# holiday_tree_schematic.net
KiCad netlist of a schematic drawn in Altium Designer
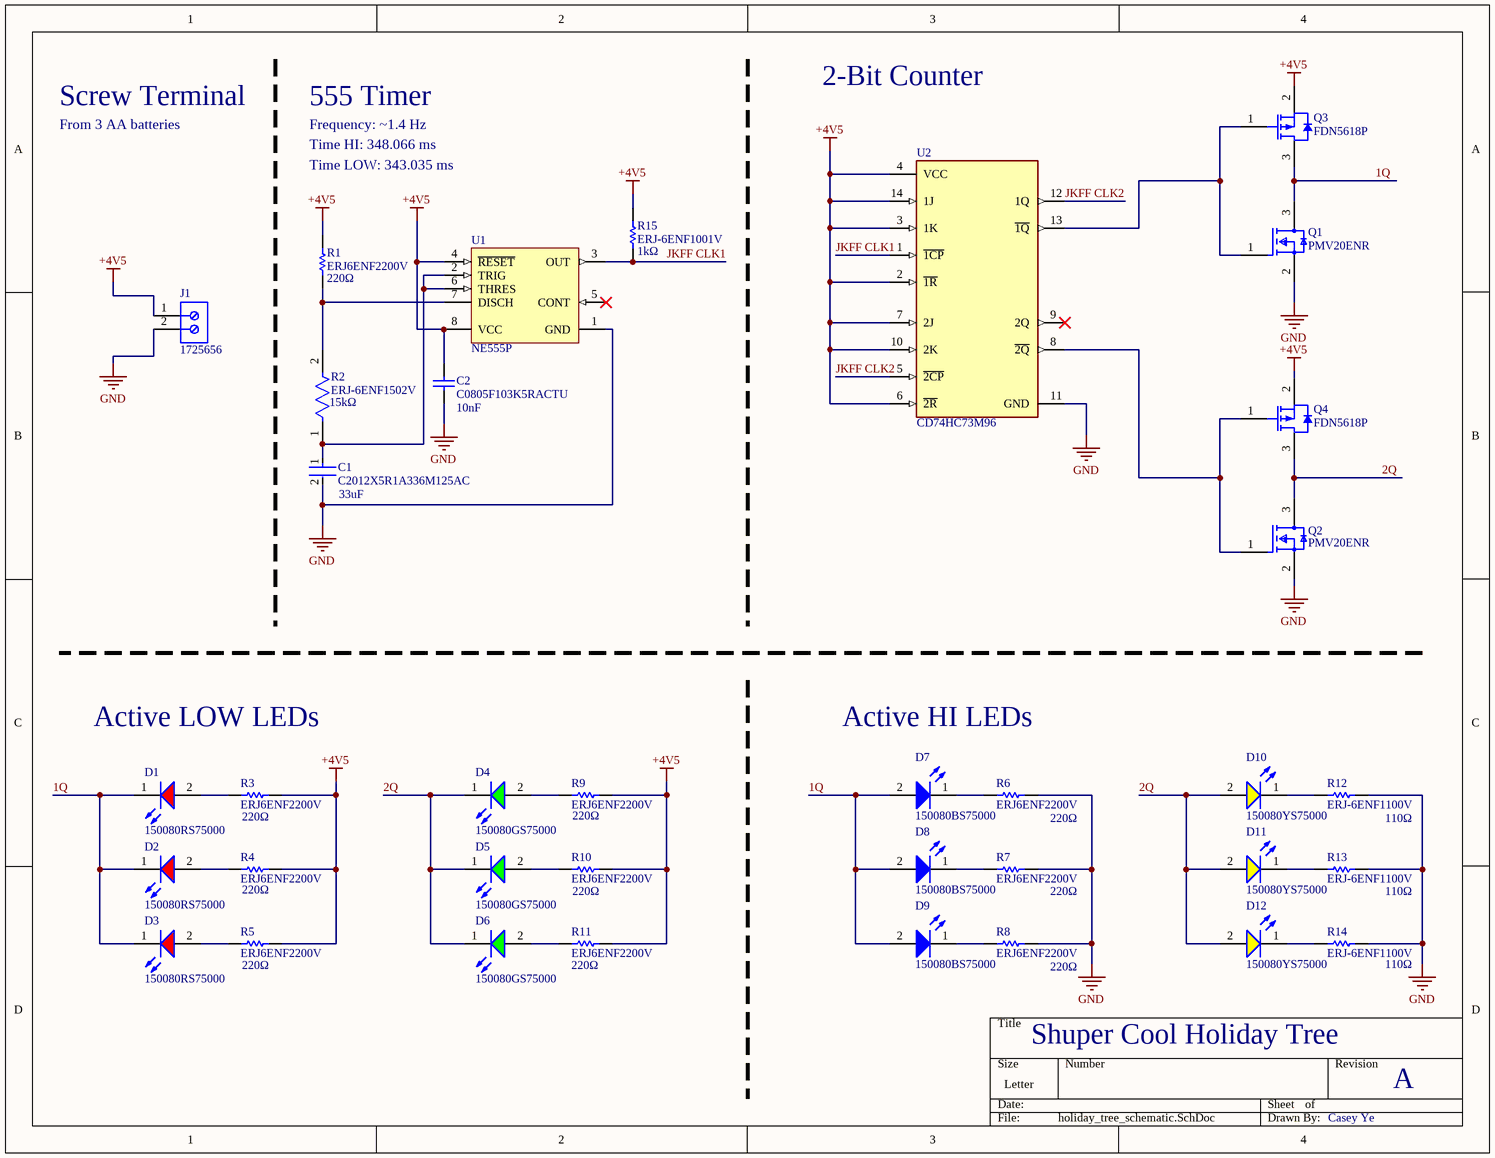
[diagram p0: holiday_tree_schematic.SchDoc]

(export (version "E")
  (design (tool "Eeschema 10.0.6"))
  (components
    (comp (ref "C1")
      (value "C2012X5R1A336M125AC")
      (footprint "FP-C2012-125-0_2-IPC_A")
      (description "Multilayer Ceramic Capacitors 33μF ±20% 10V X5R SMD 0805")
      (fields (field (name "TOLERANCE") "20%"))
      (libsource (lib "Altium Content Vault") (part "b4654b650e69147ec39a6b967a45e02"))
    )
    (comp (ref "C2")
      (value "C0805F103K5RACTU")
      (footprint "CAPC2013X100X50NL20T25")
      (fields (field (name "MANUFACTURER") "Kemet"))
      (libsource (lib "Altium Content Vault") (part "CAP"))
    )
    (comp (ref "D1")
      (value "150080RS75000")
      (footprint "WL-SMCW_0805_150080xx75000")
      (description "LED Uni-Color Red 630nm 2-Pin Chip 0805(2012Metric) T/R")
      (libsource (lib "Altium Content Vault") (part "LED_Red_2A-1K"))
    )
    (comp (ref "D2")
      (value "150080RS75000")
      (footprint "WL-SMCW_0805_150080xx75000")
      (description "LED Uni-Color Red 630nm 2-Pin Chip 0805(2012Metric) T/R")
      (libsource (lib "Altium Content Vault") (part "LED_Red_2A-1K"))
    )
    (comp (ref "D3")
      (value "150080RS75000")
      (footprint "WL-SMCW_0805_150080xx75000")
      (description "LED Uni-Color Red 630nm 2-Pin Chip 0805(2012Metric) T/R")
      (libsource (lib "Altium Content Vault") (part "LED_Red_2A-1K"))
    )
    (comp (ref "D4")
      (value "150080GS75000")
      (footprint "WL-SMCW_0805_150080xx75000")
      (description "WURTH ELEKTRONIK - 150080GS75000 - LED, Green, SMD, 0805, 30 mA, 3.2 V, 520 nm")
      (libsource (lib "Altium Content Vault") (part "LED_Green_2A-1K"))
    )
    (comp (ref "D5")
      (value "150080GS75000")
      (footprint "WL-SMCW_0805_150080xx75000")
      (description "WURTH ELEKTRONIK - 150080GS75000 - LED, Green, SMD, 0805, 30 mA, 3.2 V, 520 nm")
      (libsource (lib "Altium Content Vault") (part "LED_Green_2A-1K"))
    )
    (comp (ref "D6")
      (value "150080GS75000")
      (footprint "WL-SMCW_0805_150080xx75000")
      (description "WURTH ELEKTRONIK - 150080GS75000 - LED, Green, SMD, 0805, 30 mA, 3.2 V, 520 nm")
      (libsource (lib "Altium Content Vault") (part "LED_Green_2A-1K"))
    )
    (comp (ref "D7")
      (value "150080BS75000")
      (footprint "WL-SMCW_0805_150080xx75000")
      (description "Led, Blue, 470 Nm, 3.2 V, 30 Ma, 145 Mcd Rohs Compliant: Yes")
      (libsource (lib "Altium Content Vault") (part "LED_Blue_2A-1K"))
    )
    (comp (ref "D8")
      (value "150080BS75000")
      (footprint "WL-SMCW_0805_150080xx75000")
      (description "Led, Blue, 470 Nm, 3.2 V, 30 Ma, 145 Mcd Rohs Compliant: Yes")
      (libsource (lib "Altium Content Vault") (part "LED_Blue_2A-1K"))
    )
    (comp (ref "D9")
      (value "150080BS75000")
      (footprint "WL-SMCW_0805_150080xx75000")
      (description "Led, Blue, 470 Nm, 3.2 V, 30 Ma, 145 Mcd Rohs Compliant: Yes")
      (libsource (lib "Altium Content Vault") (part "LED_Blue_2A-1K"))
    )
    (comp (ref "D10")
      (value "150080YS75000")
      (footprint "WL-SMCW_0805_150080xx75000")
      (description "2 V Yellow LED 2012 (0805) SMD, Wurth Elektronik WL-SMCW 150080YS75000")
      (libsource (lib "Altium Content Vault") (part "LED_Yellow_2A-1K"))
    )
    (comp (ref "D11")
      (value "150080YS75000")
      (footprint "WL-SMCW_0805_150080xx75000")
      (description "2 V Yellow LED 2012 (0805) SMD, Wurth Elektronik WL-SMCW 150080YS75000")
      (libsource (lib "Altium Content Vault") (part "LED_Yellow_2A-1K"))
    )
    (comp (ref "D12")
      (value "150080YS75000")
      (footprint "WL-SMCW_0805_150080xx75000")
      (description "2 V Yellow LED 2012 (0805) SMD, Wurth Elektronik WL-SMCW 150080YS75000")
      (libsource (lib "Altium Content Vault") (part "LED_Yellow_2A-1K"))
    )
    (comp (ref "J1")
      (value "1725656")
      (footprint "PHOE-1725656-2")
      (description "Male Header, Pitch 2.54 mm, 1 x 2 Position, Height 9 mm, Tail Length 3.5 mm")
      (fields (field (name "MANUFACTURER") "Phoenix Contact"))
      (libsource (lib "Altium Content Vault") (part "CN-1P-F-TB2"))
    )
    (comp (ref "Q1")
      (value "PMV20ENR")
      (footprint "FP-SOT23-MFG")
      (description "MOSFET N-CH 30V SOT23")
      (libsource (lib "Altium Content Vault") (part "0a9ea7c96deaaede766a5b531c28de0"))
    )
    (comp (ref "Q2")
      (value "PMV20ENR")
      (footprint "FP-SOT23-MFG")
      (description "MOSFET N-CH 30V SOT23")
      (libsource (lib "Altium Content Vault") (part "0a9ea7c96deaaede766a5b531c28de0"))
    )
    (comp (ref "Q3")
      (value "FDN5618P")
      (footprint "FAIR-SSOT3L-3_V")
      (description "P-Channel Logic Level PowerTrench(R) MOSFET, -60 V, -1.25 A, 3-Pin SOT23, RoHS, Tape and Reel")
      (fields (field (name "MANUFACTURER") "Fairchild Semiconductor"))
      (libsource (lib "Altium Content Vault") (part "PEMOS-GSD-3"))
    )
    (comp (ref "Q4")
      (value "FDN5618P")
      (footprint "FAIR-SSOT3L-3_V")
      (description "P-Channel Logic Level PowerTrench(R) MOSFET, -60 V, -1.25 A, 3-Pin SOT23, RoHS, Tape and Reel")
      (fields (field (name "MANUFACTURER") "Fairchild Semiconductor"))
      (libsource (lib "Altium Content Vault") (part "PEMOS-GSD-3"))
    )
    (comp (ref "R1")
      (value "ERJ6ENF2200V")
      (footprint "RESC2013X70X40NL20T20")
      (fields (field (name "MANUFACTURER") "Panasonic"))
      (libsource (lib "Altium Content Vault") (part "RES"))
    )
    (comp (ref "R2")
      (value "ERJ-6ENF1502V")
      (footprint "FP-ERJ6EN-IPC_C")
      (description "RES SMD 15K OHM 1% 1/8W 0805")
      (fields (field (name "TOLERANCE") "1%"))
      (libsource (lib "Altium Content Vault") (part "8db39607336c341a927600551d01821"))
    )
    (comp (ref "R3")
      (value "ERJ6ENF2200V")
      (footprint "RESC2013X70X40NL20T20")
      (fields (field (name "MANUFACTURER") "Panasonic"))
      (libsource (lib "Altium Content Vault") (part "RES"))
    )
    (comp (ref "R4")
      (value "ERJ6ENF2200V")
      (footprint "RESC2013X70X40NL20T20")
      (fields (field (name "MANUFACTURER") "Panasonic"))
      (libsource (lib "Altium Content Vault") (part "RES"))
    )
    (comp (ref "R5")
      (value "ERJ6ENF2200V")
      (footprint "RESC2013X70X40NL20T20")
      (fields (field (name "MANUFACTURER") "Panasonic"))
      (libsource (lib "Altium Content Vault") (part "RES"))
    )
    (comp (ref "R6")
      (value "ERJ6ENF2200V")
      (footprint "RESC2013X70X40NL20T20")
      (fields (field (name "MANUFACTURER") "Panasonic"))
      (libsource (lib "Altium Content Vault") (part "RES"))
    )
    (comp (ref "R7")
      (value "ERJ6ENF2200V")
      (footprint "RESC2013X70X40NL20T20")
      (fields (field (name "MANUFACTURER") "Panasonic"))
      (libsource (lib "Altium Content Vault") (part "RES"))
    )
    (comp (ref "R8")
      (value "ERJ6ENF2200V")
      (footprint "RESC2013X70X40NL20T20")
      (fields (field (name "MANUFACTURER") "Panasonic"))
      (libsource (lib "Altium Content Vault") (part "RES"))
    )
    (comp (ref "R9")
      (value "ERJ6ENF2200V")
      (footprint "RESC2013X70X40NL20T20")
      (fields (field (name "MANUFACTURER") "Panasonic"))
      (libsource (lib "Altium Content Vault") (part "RES"))
    )
    (comp (ref "R10")
      (value "ERJ6ENF2200V")
      (footprint "RESC2013X70X40NL20T20")
      (fields (field (name "MANUFACTURER") "Panasonic"))
      (libsource (lib "Altium Content Vault") (part "RES"))
    )
    (comp (ref "R11")
      (value "ERJ6ENF2200V")
      (footprint "RESC2013X70X40NL20T20")
      (fields (field (name "MANUFACTURER") "Panasonic"))
      (libsource (lib "Altium Content Vault") (part "RES"))
    )
    (comp (ref "R12")
      (value "ERJ-6ENF1100V")
      (footprint "RESC2013X70X40NL20T20")
      (fields (field (name "MANUFACTURER") "Panasonic"))
      (libsource (lib "Altium Content Vault") (part "RES"))
    )
    (comp (ref "R13")
      (value "ERJ-6ENF1100V")
      (footprint "RESC2013X70X40NL20T20")
      (fields (field (name "MANUFACTURER") "Panasonic"))
      (libsource (lib "Altium Content Vault") (part "RES"))
    )
    (comp (ref "R14")
      (value "ERJ-6ENF1100V")
      (footprint "RESC2013X70X40NL20T20")
      (fields (field (name "MANUFACTURER") "Panasonic"))
      (libsource (lib "Altium Content Vault") (part "RES"))
    )
    (comp (ref "R15")
      (value "ERJ-6ENF1001V")
      (footprint "RESC2013X70X40ML20T20")
      (description "Chip Resistor, 1 KOhm, +/- 1%, 0.125 W, -55 to 155 degC, 0805 (2012 Metric), RoHS, Tape and Reel")
      (fields (field (name "MANUFACTURER") "Panasonic"))
      (libsource (lib "Altium Content Vault") (part "RES-2"))
    )
    (comp (ref "U1")
      (value "NE555P")
      (footprint "P0008A")
      (description "Precision Timer, 4.5 to 16 V, 0 to 70 degC, 8-Pin DIP, Pb-Free, Tube")
      (fields (field (name "MANUFACTURER") "TexasInstruments"))
      (libsource (lib "Altium Content Vault") (part "TI-NE555-P8"))
    )
    (comp (ref "U2")
      (value "CD74HC73M96")
      (footprint "FP-D0014A-IPC_B")
      (description "IC FF JK TYPE DUAL 1BIT 14SOIC")
      (libsource (lib "Altium Content Vault") (part "f8ab0c232ecaa4f820ac0ac336fa3bc"))
    )
  )
  (nets
    (net (code "1") (name "+4V5") (class "Default")
      (node (ref "C2") (pin "2") (pinfunction "2_2") (pintype "passive"))
      (node (ref "J1") (pin "1") (pinfunction "1_1") (pintype "passive"))
      (node (ref "Q3") (pin "2") (pinfunction "SOURCE_2") (pintype "passive"))
      (node (ref "Q4") (pin "2") (pinfunction "SOURCE_2") (pintype "passive"))
      (node (ref "R1") (pin "2") (pinfunction "2_2") (pintype "passive"))
      (node (ref "R10") (pin "2") (pinfunction "2_2") (pintype "passive"))
      (node (ref "R11") (pin "2") (pinfunction "2_2") (pintype "passive"))
      (node (ref "R15") (pin "2") (pinfunction "2_2") (pintype "passive"))
      (node (ref "R3") (pin "2") (pinfunction "2_2") (pintype "passive"))
      (node (ref "R4") (pin "2") (pinfunction "2_2") (pintype "passive"))
      (node (ref "R5") (pin "2") (pinfunction "2_2") (pintype "passive"))
      (node (ref "R9") (pin "2") (pinfunction "2_2") (pintype "passive"))
      (node (ref "U1") (pin "4") (pinfunction "~{RESET}_4") (pintype "input"))
      (node (ref "U1") (pin "8") (pinfunction "VCC_8") (pintype "power_in"))
      (node (ref "U2") (pin "10") (pinfunction "2K_10") (pintype "input"))
      (node (ref "U2") (pin "14") (pinfunction "1J_14") (pintype "input"))
      (node (ref "U2") (pin "2") (pinfunction "~{1R}_2") (pintype "input"))
      (node (ref "U2") (pin "3") (pinfunction "1K_3") (pintype "input"))
      (node (ref "U2") (pin "4") (pinfunction "VCC_4") (pintype "power_in"))
      (node (ref "U2") (pin "6") (pinfunction "~{2R}_6") (pintype "input"))
      (node (ref "U2") (pin "7") (pinfunction "2J_7") (pintype "input"))
    )
    (net (code "2") (name "/1Q") (class "Default")
      (node (ref "D1") (pin "1") (pinfunction "K_1") (pintype "passive"))
      (node (ref "D2") (pin "1") (pinfunction "K_1") (pintype "passive"))
      (node (ref "D3") (pin "1") (pinfunction "K_1") (pintype "passive"))
      (node (ref "D7") (pin "2") (pinfunction "A_2") (pintype "passive"))
      (node (ref "D8") (pin "2") (pinfunction "A_2") (pintype "passive"))
      (node (ref "D9") (pin "2") (pinfunction "A_2") (pintype "passive"))
      (node (ref "Q1") (pin "3") (pinfunction "D_3") (pintype "passive"))
      (node (ref "Q3") (pin "3") (pinfunction "DRAIN_3") (pintype "passive"))
    )
    (net (code "3") (name "/2Q") (class "Default")
      (node (ref "D10") (pin "2") (pinfunction "A_2") (pintype "passive"))
      (node (ref "D11") (pin "2") (pinfunction "A_2") (pintype "passive"))
      (node (ref "D12") (pin "2") (pinfunction "A_2") (pintype "passive"))
      (node (ref "D4") (pin "1") (pinfunction "K_1") (pintype "passive"))
      (node (ref "D5") (pin "1") (pinfunction "K_1") (pintype "passive"))
      (node (ref "D6") (pin "1") (pinfunction "K_1") (pintype "passive"))
      (node (ref "Q2") (pin "3") (pinfunction "D_3") (pintype "passive"))
      (node (ref "Q4") (pin "3") (pinfunction "DRAIN_3") (pintype "passive"))
    )
    (net (code "4") (name "/JKFF CLK1") (class "Default")
      (node (ref "R15") (pin "1") (pinfunction "1_1") (pintype "passive"))
      (node (ref "U1") (pin "3") (pinfunction "OUT_3") (pintype "output"))
      (node (ref "U2") (pin "1") (pinfunction "~{1CP}_1") (pintype "input"))
    )
    (net (code "5") (name "/JKFF CLK2") (class "Default")
      (node (ref "U2") (pin "12") (pinfunction "1Q_12") (pintype "output"))
      (node (ref "U2") (pin "5") (pinfunction "~{2CP}_5") (pintype "input"))
    )
    (net (code "6") (name "GND") (class "Default")
      (node (ref "C1") (pin "2") (pinfunction "2_2") (pintype "passive"))
      (node (ref "C2") (pin "1") (pinfunction "1_1") (pintype "passive"))
      (node (ref "J1") (pin "2") (pinfunction "2_2") (pintype "passive"))
      (node (ref "Q1") (pin "2") (pinfunction "S_2") (pintype "passive"))
      (node (ref "Q2") (pin "2") (pinfunction "S_2") (pintype "passive"))
      (node (ref "R12") (pin "2") (pinfunction "2_2") (pintype "passive"))
      (node (ref "R13") (pin "2") (pinfunction "2_2") (pintype "passive"))
      (node (ref "R14") (pin "2") (pinfunction "2_2") (pintype "passive"))
      (node (ref "R6") (pin "2") (pinfunction "2_2") (pintype "passive"))
      (node (ref "R7") (pin "2") (pinfunction "2_2") (pintype "passive"))
      (node (ref "R8") (pin "2") (pinfunction "2_2") (pintype "passive"))
      (node (ref "U1") (pin "1") (pinfunction "GND_1") (pintype "power_in"))
      (node (ref "U2") (pin "11") (pinfunction "GND_11") (pintype "power_in"))
    )
    (net (code "7") (name "Net-(D1-A)") (class "Default")
      (node (ref "D1") (pin "2") (pinfunction "A_2") (pintype "passive"))
      (node (ref "R3") (pin "1") (pinfunction "1_1") (pintype "passive"))
    )
    (net (code "8") (name "Net-(D2-A)") (class "Default")
      (node (ref "D2") (pin "2") (pinfunction "A_2") (pintype "passive"))
      (node (ref "R4") (pin "1") (pinfunction "1_1") (pintype "passive"))
    )
    (net (code "9") (name "Net-(D3-A)") (class "Default")
      (node (ref "D3") (pin "2") (pinfunction "A_2") (pintype "passive"))
      (node (ref "R5") (pin "1") (pinfunction "1_1") (pintype "passive"))
    )
    (net (code "10") (name "Net-(D4-A)") (class "Default")
      (node (ref "D4") (pin "2") (pinfunction "A_2") (pintype "passive"))
      (node (ref "R9") (pin "1") (pinfunction "1_1") (pintype "passive"))
    )
    (net (code "11") (name "Net-(D5-A)") (class "Default")
      (node (ref "D5") (pin "2") (pinfunction "A_2") (pintype "passive"))
      (node (ref "R10") (pin "1") (pinfunction "1_1") (pintype "passive"))
    )
    (net (code "12") (name "Net-(D6-A)") (class "Default")
      (node (ref "D6") (pin "2") (pinfunction "A_2") (pintype "passive"))
      (node (ref "R11") (pin "1") (pinfunction "1_1") (pintype "passive"))
    )
    (net (code "13") (name "Net-(D7-K)") (class "Default")
      (node (ref "D7") (pin "1") (pinfunction "K_1") (pintype "passive"))
      (node (ref "R6") (pin "1") (pinfunction "1_1") (pintype "passive"))
    )
    (net (code "14") (name "Net-(D8-K)") (class "Default")
      (node (ref "D8") (pin "1") (pinfunction "K_1") (pintype "passive"))
      (node (ref "R7") (pin "1") (pinfunction "1_1") (pintype "passive"))
    )
    (net (code "15") (name "Net-(D9-K)") (class "Default")
      (node (ref "D9") (pin "1") (pinfunction "K_1") (pintype "passive"))
      (node (ref "R8") (pin "1") (pinfunction "1_1") (pintype "passive"))
    )
    (net (code "16") (name "Net-(D10-K)") (class "Default")
      (node (ref "D10") (pin "1") (pinfunction "K_1") (pintype "passive"))
      (node (ref "R12") (pin "1") (pinfunction "1_1") (pintype "passive"))
    )
    (net (code "17") (name "Net-(D11-K)") (class "Default")
      (node (ref "D11") (pin "1") (pinfunction "K_1") (pintype "passive"))
      (node (ref "R13") (pin "1") (pinfunction "1_1") (pintype "passive"))
    )
    (net (code "18") (name "Net-(D12-K)") (class "Default")
      (node (ref "D12") (pin "1") (pinfunction "K_1") (pintype "passive"))
      (node (ref "R14") (pin "1") (pinfunction "1_1") (pintype "passive"))
    )
    (net (code "19") (name "Net-(Q1-G)") (class "Default")
      (node (ref "Q1") (pin "1") (pinfunction "G_1") (pintype "passive"))
      (node (ref "Q3") (pin "1") (pinfunction "GATE_1") (pintype "passive"))
      (node (ref "U2") (pin "13") (pinfunction "~{1Q}_13") (pintype "output"))
    )
    (net (code "20") (name "Net-(Q2-G)") (class "Default")
      (node (ref "Q2") (pin "1") (pinfunction "G_1") (pintype "passive"))
      (node (ref "Q4") (pin "1") (pinfunction "GATE_1") (pintype "passive"))
      (node (ref "U2") (pin "8") (pinfunction "~{2Q}_8") (pintype "output"))
    )
    (net (code "21") (name "Net-(U1-DISCH)") (class "Default")
      (node (ref "R1") (pin "1") (pinfunction "1_1") (pintype "passive"))
      (node (ref "R2") (pin "2") (pinfunction "2_2") (pintype "passive"))
      (node (ref "U1") (pin "7") (pinfunction "DISCH_7") (pintype "open_collector"))
    )
    (net (code "22") (name "Net-(U1-THRES)") (class "Default")
      (node (ref "C1") (pin "1") (pinfunction "1_1") (pintype "passive"))
      (node (ref "R2") (pin "1") (pinfunction "1_1") (pintype "passive"))
      (node (ref "U1") (pin "2") (pinfunction "TRIG_2") (pintype "input"))
      (node (ref "U1") (pin "6") (pinfunction "THRES_6") (pintype "input"))
    )
    (net (code "23") (name "unconnected-(U1-CONT-Pad5)") (class "Default")
      (node (ref "U1") (pin "5") (pinfunction "CONT_5") (pintype "input+no_connect"))
    )
    (net (code "24") (name "unconnected-(U2-2Q-Pad9)") (class "Default")
      (node (ref "U2") (pin "9") (pinfunction "2Q_9") (pintype "output+no_connect"))
    )
  )
)
